# SMA.net
KiCad netlist of a schematic drawn in Altium Designer
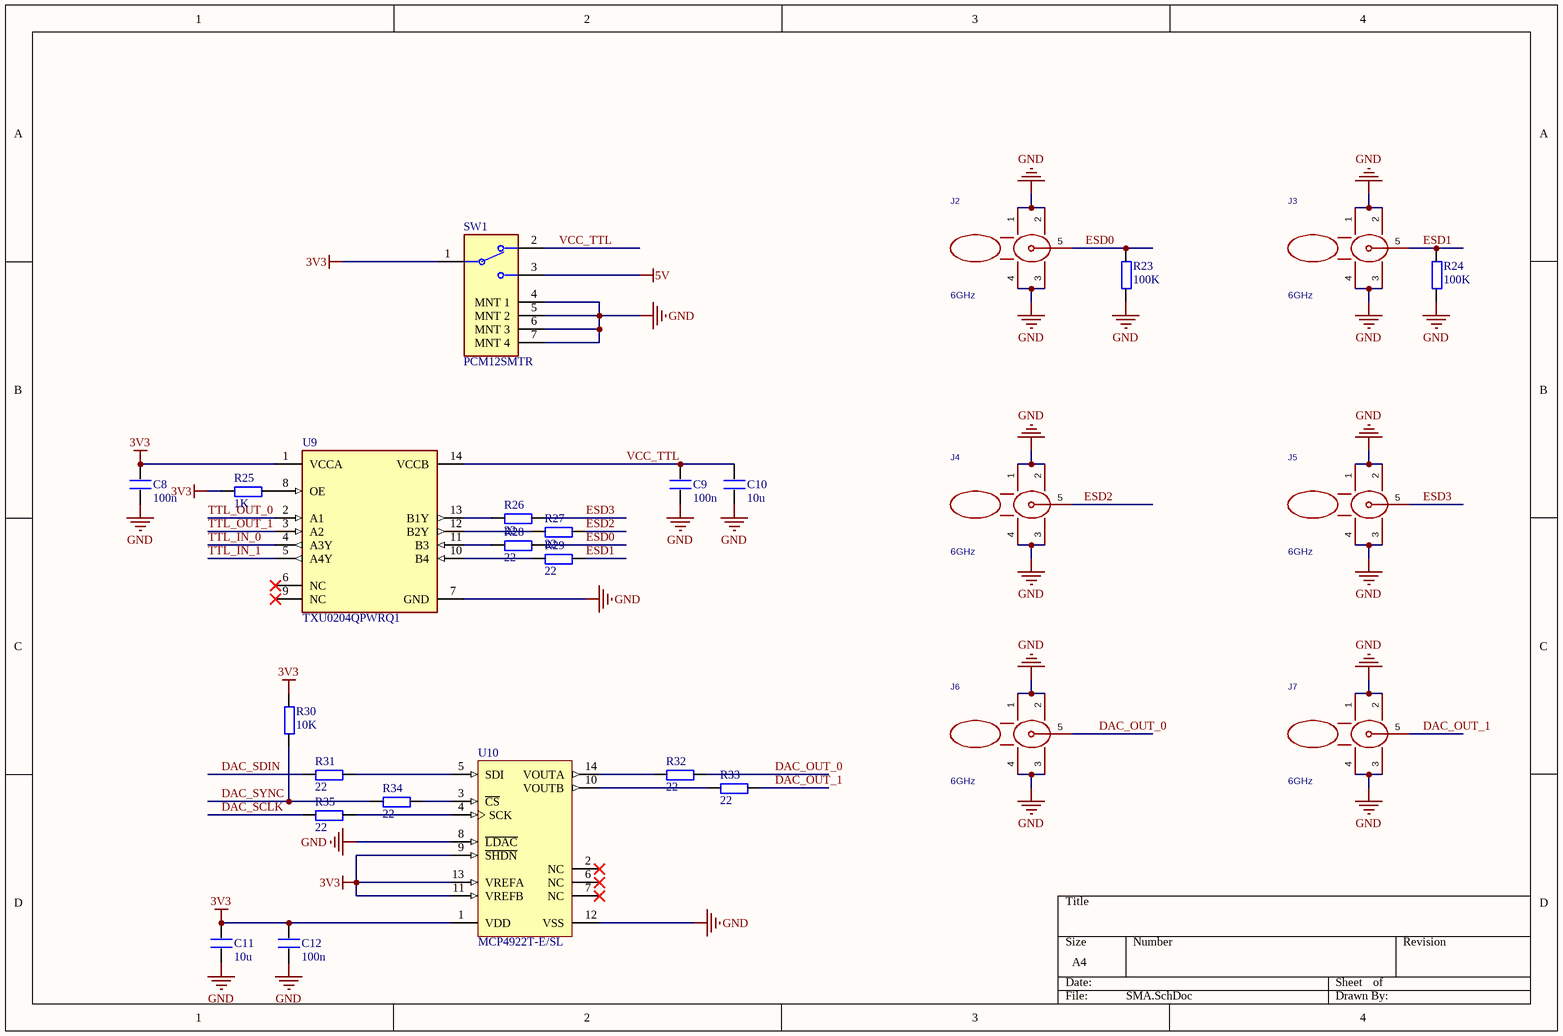
[diagram p0: SMA.SchDoc]

(export (version "E")
  (design (tool "Eeschema 10.0.6"))
  (components
    (comp (ref "C8") (value "100n") (footprint "C 0402_L") (libsource (lib "ZYNQ_开发板") (part "C_1")))
    (comp (ref "C9") (value "100n") (footprint "C 0402_L") (libsource (lib "ZYNQ_开发板") (part "C_1")))
    (comp (ref "C10") (value "10u") (footprint "C 0603_L") (libsource (lib "ZYNQ_开发板") (part "C_1")))
    (comp (ref "C11") (value "10u") (footprint "C 0603_L") (libsource (lib "ZYNQ_开发板") (part "C_1")))
    (comp (ref "C12") (value "100n") (footprint "C 0402_L") (libsource (lib "ZYNQ_开发板") (part "C_1")))
    (comp (ref "J2")
      (value "6GHz")
      (footprint "PCBComponent_1 - duplicate2")
      (fields
        (field (name "MANUFACTURER") "BAT WIRELESS(蝙蝠无线)")
        (field (name "MANUFACTURER PART") "BWSMA-KE-Z001")
      )
      (libsource (lib "altium-import") (part "root_0_BWSMA-KE-Z001_C496549_"))
    )
    (comp (ref "J3")
      (value "6GHz")
      (footprint "PCBComponent_1 - duplicate2")
      (fields
        (field (name "MANUFACTURER") "BAT WIRELESS(蝙蝠无线)")
        (field (name "MANUFACTURER PART") "BWSMA-KE-Z001")
      )
      (libsource (lib "altium-import") (part "root_0_BWSMA-KE-Z001_C496549_"))
    )
    (comp (ref "J4")
      (value "6GHz")
      (footprint "PCBComponent_1 - duplicate2")
      (fields
        (field (name "MANUFACTURER") "BAT WIRELESS(蝙蝠无线)")
        (field (name "MANUFACTURER PART") "BWSMA-KE-Z001")
      )
      (libsource (lib "altium-import") (part "root_0_BWSMA-KE-Z001_C496549_"))
    )
    (comp (ref "J5")
      (value "6GHz")
      (footprint "PCBComponent_1 - duplicate2")
      (fields
        (field (name "MANUFACTURER") "BAT WIRELESS(蝙蝠无线)")
        (field (name "MANUFACTURER PART") "BWSMA-KE-Z001")
      )
      (libsource (lib "altium-import") (part "root_0_BWSMA-KE-Z001_C496549_"))
    )
    (comp (ref "J6")
      (value "6GHz")
      (footprint "PCBComponent_1 - duplicate2")
      (fields
        (field (name "MANUFACTURER") "BAT WIRELESS(蝙蝠无线)")
        (field (name "MANUFACTURER PART") "BWSMA-KE-Z001")
      )
      (libsource (lib "altium-import") (part "root_0_BWSMA-KE-Z001_C496549_"))
    )
    (comp (ref "J7")
      (value "6GHz")
      (footprint "PCBComponent_1 - duplicate2")
      (fields
        (field (name "MANUFACTURER") "BAT WIRELESS(蝙蝠无线)")
        (field (name "MANUFACTURER PART") "BWSMA-KE-Z001")
      )
      (libsource (lib "altium-import") (part "root_0_BWSMA-KE-Z001_C496549_"))
    )
    (comp (ref "R23") (value "100K") (footprint "R 0402_L") (libsource (lib "ZYNQ_开发板") (part "R")))
    (comp (ref "R24") (value "100K") (footprint "R 0402_L") (libsource (lib "ZYNQ_开发板") (part "R")))
    (comp (ref "R25") (value "1K") (footprint "R 0402_L") (libsource (lib "ZYNQ_开发板") (part "R")))
    (comp (ref "R26") (value "22") (footprint "R 0402_L") (libsource (lib "ZYNQ_开发板") (part "R")))
    (comp (ref "R27") (value "22") (footprint "R 0402_L") (libsource (lib "ZYNQ_开发板") (part "R")))
    (comp (ref "R28") (value "22") (footprint "R 0402_L") (libsource (lib "ZYNQ_开发板") (part "R")))
    (comp (ref "R29") (value "22") (footprint "R 0402_L") (libsource (lib "ZYNQ_开发板") (part "R")))
    (comp (ref "R30") (value "10K") (footprint "R 0402_L") (libsource (lib "ZYNQ_开发板") (part "R")))
    (comp (ref "R31") (value "22") (footprint "R 0402_L") (libsource (lib "ZYNQ_开发板") (part "R")))
    (comp (ref "R32") (value "22") (footprint "R 0402_L") (libsource (lib "ZYNQ_开发板") (part "R")))
    (comp (ref "R33") (value "22") (footprint "R 0402_L") (libsource (lib "ZYNQ_开发板") (part "R")))
    (comp (ref "R34") (value "22") (footprint "R 0402_L") (libsource (lib "ZYNQ_开发板") (part "R")))
    (comp (ref "R35") (value "22") (footprint "R 0402_L") (libsource (lib "ZYNQ_开发板") (part "R")))
    (comp (ref "SW1")
      (value "PCM12SMTR")
      (footprint "FP-PCM12SMTR-MFG")
      (description "SWITCH SLIDE SPDT 300MA 6V")
      (libsource (lib "Altium Content Vault") (part "1a3f67d7e2b5469b171eeab59ffb4d2"))
    )
    (comp (ref "U9")
      (value "TXU0204QPWRQ1")
      (footprint "FP-PW0014A-MFG")
      (description "TXU0204QPWRQ1 Automotive four-channel fixed multidirectional level shifter 14-TSSOP -40 to 125")
      (libsource (lib "Altium Content Vault") (part "44858a714c9b6f832d6c8bf1a60bf28"))
    )
    (comp (ref "U10")
      (value "MCP4922T-E/SL")
      (footprint "SOIC-SL14_M")
      (description "12-Bit DAC with SPI Interface, 14-Pin SOIC 150mil, Extended Temperature, Tape and Reel")
      (libsource (lib "Altium Content Vault") (part "CON-DAC-MCP4922-14"))
    )
  )
  (nets
    (net (code "1") (name "/DAC_OUT_0") (class "Default")
      (node (ref "J6") (pin "5") (pinfunction "5_5") (pintype "passive"))
      (node (ref "R32") (pin "2") (pintype "passive"))
    )
    (net (code "2") (name "/DAC_OUT_1") (class "Default")
      (node (ref "J7") (pin "5") (pinfunction "5_5") (pintype "passive"))
      (node (ref "R33") (pin "2") (pintype "passive"))
    )
    (net (code "3") (name "/DAC_SCLK") (class "Default") (node (ref "R35") (pin "1") (pintype "passive")))
    (net (code "4") (name "/DAC_SDIN") (class "Default") (node (ref "R31") (pin "1") (pintype "passive")))
    (net (code "5") (name "/DAC_SYNC") (class "Default")
      (node (ref "R30") (pin "1") (pintype "passive"))
      (node (ref "R34") (pin "1") (pintype "passive"))
    )
    (net (code "6") (name "/ESD0") (class "Default")
      (node (ref "J2") (pin "5") (pinfunction "5_5") (pintype "passive"))
      (node (ref "R23") (pin "2") (pintype "passive"))
      (node (ref "R28") (pin "2") (pintype "passive"))
    )
    (net (code "7") (name "/ESD1") (class "Default")
      (node (ref "J3") (pin "5") (pinfunction "5_5") (pintype "passive"))
      (node (ref "R24") (pin "2") (pintype "passive"))
      (node (ref "R29") (pin "2") (pintype "passive"))
    )
    (net (code "8") (name "/ESD2") (class "Default")
      (node (ref "J4") (pin "5") (pinfunction "5_5") (pintype "passive"))
      (node (ref "R27") (pin "2") (pintype "passive"))
    )
    (net (code "9") (name "/ESD3") (class "Default")
      (node (ref "J5") (pin "5") (pinfunction "5_5") (pintype "passive"))
      (node (ref "R26") (pin "2") (pintype "passive"))
    )
    (net (code "10") (name "/TTL_IN_0") (class "Default")
      (node (ref "U9") (pin "4") (pinfunction "A3Y_4") (pintype "output"))
    )
    (net (code "11") (name "/TTL_IN_1") (class "Default")
      (node (ref "U9") (pin "5") (pinfunction "A4Y_5") (pintype "output"))
    )
    (net (code "12") (name "/TTL_OUT_0") (class "Default")
      (node (ref "U9") (pin "2") (pinfunction "A1_2") (pintype "input"))
    )
    (net (code "13") (name "/TTL_OUT_1") (class "Default")
      (node (ref "U9") (pin "3") (pinfunction "A2_3") (pintype "input"))
    )
    (net (code "14") (name "/VCC_TTL") (class "Default")
      (node (ref "C10") (pin "2") (pintype "passive"))
      (node (ref "C9") (pin "2") (pintype "passive"))
      (node (ref "SW1") (pin "2") (pinfunction "2_2") (pintype "passive"))
      (node (ref "U9") (pin "14") (pinfunction "VCCB_14") (pintype "power_in"))
    )
    (net (code "15") (name "3V3") (class "Default")
      (node (ref "C11") (pin "2") (pintype "passive"))
      (node (ref "C12") (pin "2") (pintype "passive"))
      (node (ref "C8") (pin "2") (pintype "passive"))
      (node (ref "R25") (pin "1") (pintype "passive"))
      (node (ref "R30") (pin "2") (pintype "passive"))
      (node (ref "SW1") (pin "1") (pinfunction "1_1") (pintype "passive"))
      (node (ref "U10") (pin "1") (pinfunction "VDD_1") (pintype "power_in"))
      (node (ref "U10") (pin "11") (pinfunction "VREFB_11") (pintype "input"))
      (node (ref "U10") (pin "13") (pinfunction "VREFA_13") (pintype "input"))
      (node (ref "U10") (pin "9") (pinfunction "~{SHDN}_9") (pintype "input"))
      (node (ref "U9") (pin "1") (pinfunction "VCCA_1") (pintype "power_in"))
    )
    (net (code "16") (name "5V") (class "Default")
      (node (ref "SW1") (pin "3") (pinfunction "3_3") (pintype "passive"))
    )
    (net (code "17") (name "GND") (class "Default")
      (node (ref "C10") (pin "1") (pintype "passive"))
      (node (ref "C11") (pin "1") (pintype "passive"))
      (node (ref "C12") (pin "1") (pintype "passive"))
      (node (ref "C8") (pin "1") (pintype "passive"))
      (node (ref "C9") (pin "1") (pintype "passive"))
      (node (ref "J2") (pin "1") (pinfunction "1_1") (pintype "passive"))
      (node (ref "J2") (pin "2") (pinfunction "2_2") (pintype "passive"))
      (node (ref "J2") (pin "3") (pinfunction "3_3") (pintype "passive"))
      (node (ref "J2") (pin "4") (pinfunction "4_4") (pintype "passive"))
      (node (ref "J3") (pin "1") (pinfunction "1_1") (pintype "passive"))
      (node (ref "J3") (pin "2") (pinfunction "2_2") (pintype "passive"))
      (node (ref "J3") (pin "3") (pinfunction "3_3") (pintype "passive"))
      (node (ref "J3") (pin "4") (pinfunction "4_4") (pintype "passive"))
      (node (ref "J4") (pin "1") (pinfunction "1_1") (pintype "passive"))
      (node (ref "J4") (pin "2") (pinfunction "2_2") (pintype "passive"))
      (node (ref "J4") (pin "3") (pinfunction "3_3") (pintype "passive"))
      (node (ref "J4") (pin "4") (pinfunction "4_4") (pintype "passive"))
      (node (ref "J5") (pin "1") (pinfunction "1_1") (pintype "passive"))
      (node (ref "J5") (pin "2") (pinfunction "2_2") (pintype "passive"))
      (node (ref "J5") (pin "3") (pinfunction "3_3") (pintype "passive"))
      (node (ref "J5") (pin "4") (pinfunction "4_4") (pintype "passive"))
      (node (ref "J6") (pin "1") (pinfunction "1_1") (pintype "passive"))
      (node (ref "J6") (pin "2") (pinfunction "2_2") (pintype "passive"))
      (node (ref "J6") (pin "3") (pinfunction "3_3") (pintype "passive"))
      (node (ref "J6") (pin "4") (pinfunction "4_4") (pintype "passive"))
      (node (ref "J7") (pin "1") (pinfunction "1_1") (pintype "passive"))
      (node (ref "J7") (pin "2") (pinfunction "2_2") (pintype "passive"))
      (node (ref "J7") (pin "3") (pinfunction "3_3") (pintype "passive"))
      (node (ref "J7") (pin "4") (pinfunction "4_4") (pintype "passive"))
      (node (ref "R23") (pin "1") (pintype "passive"))
      (node (ref "R24") (pin "1") (pintype "passive"))
      (node (ref "SW1") (pin "4") (pinfunction "MNT_1_4") (pintype "passive"))
      (node (ref "SW1") (pin "5") (pinfunction "MNT_2_5") (pintype "passive"))
      (node (ref "SW1") (pin "6") (pinfunction "MNT_3_6") (pintype "passive"))
      (node (ref "SW1") (pin "7") (pinfunction "MNT_4_7") (pintype "passive"))
      (node (ref "U10") (pin "12") (pinfunction "VSS_12") (pintype "power_in"))
      (node (ref "U10") (pin "8") (pinfunction "~{LDAC}_8") (pintype "input"))
      (node (ref "U9") (pin "7") (pinfunction "GND_7") (pintype "power_in"))
    )
    (net (code "18") (name "Net-(U9-B1Y)") (class "Default")
      (node (ref "R26") (pin "1") (pintype "passive"))
      (node (ref "U9") (pin "13") (pinfunction "B1Y_13") (pintype "output"))
    )
    (net (code "19") (name "Net-(U9-B2Y)") (class "Default")
      (node (ref "R27") (pin "1") (pintype "passive"))
      (node (ref "U9") (pin "12") (pinfunction "B2Y_12") (pintype "output"))
    )
    (net (code "20") (name "Net-(U9-B3)") (class "Default")
      (node (ref "R28") (pin "1") (pintype "passive"))
      (node (ref "U9") (pin "11") (pinfunction "B3_11") (pintype "input"))
    )
    (net (code "21") (name "Net-(U9-B4)") (class "Default")
      (node (ref "R29") (pin "1") (pintype "passive"))
      (node (ref "U9") (pin "10") (pinfunction "B4_10") (pintype "input"))
    )
    (net (code "22") (name "Net-(U9-OE)") (class "Default")
      (node (ref "R25") (pin "2") (pintype "passive"))
      (node (ref "U9") (pin "8") (pinfunction "OE_8") (pintype "input"))
    )
    (net (code "23") (name "Net-(U10-SCK)") (class "Default")
      (node (ref "R35") (pin "2") (pintype "passive"))
      (node (ref "U10") (pin "4") (pinfunction "SCK_4") (pintype "input"))
    )
    (net (code "24") (name "Net-(U10-SDI)") (class "Default")
      (node (ref "R31") (pin "2") (pintype "passive"))
      (node (ref "U10") (pin "5") (pinfunction "SDI_5") (pintype "input"))
    )
    (net (code "25") (name "Net-(U10-VOUTA)") (class "Default")
      (node (ref "R32") (pin "1") (pintype "passive"))
      (node (ref "U10") (pin "14") (pinfunction "VOUTA_14") (pintype "output"))
    )
    (net (code "26") (name "Net-(U10-VOUTB)") (class "Default")
      (node (ref "R33") (pin "1") (pintype "passive"))
      (node (ref "U10") (pin "10") (pinfunction "VOUTB_10") (pintype "output"))
    )
    (net (code "27") (name "Net-(U10-~{CS})") (class "Default")
      (node (ref "R34") (pin "2") (pintype "passive"))
      (node (ref "U10") (pin "3") (pinfunction "~{CS}_3") (pintype "input"))
    )
    (net (code "28") (name "unconnected-(U9-NC-Pad6)") (class "Default")
      (node (ref "U9") (pin "6") (pinfunction "NC_6") (pintype "passive+no_connect"))
    )
    (net (code "29") (name "unconnected-(U9-NC-Pad9)") (class "Default")
      (node (ref "U9") (pin "9") (pinfunction "NC_9") (pintype "passive+no_connect"))
    )
    (net (code "30") (name "unconnected-(U10-NC-Pad2)") (class "Default")
      (node (ref "U10") (pin "2") (pinfunction "NC_2") (pintype "passive+no_connect"))
    )
    (net (code "31") (name "unconnected-(U10-NC-Pad6)") (class "Default")
      (node (ref "U10") (pin "6") (pinfunction "NC_6") (pintype "passive+no_connect"))
    )
    (net (code "32") (name "unconnected-(U10-NC-Pad7)") (class "Default")
      (node (ref "U10") (pin "7") (pinfunction "NC_7") (pintype "passive+no_connect"))
    )
  )
)
